# SmartBin.net
KiCad netlist of a schematic drawn in EasyEDA
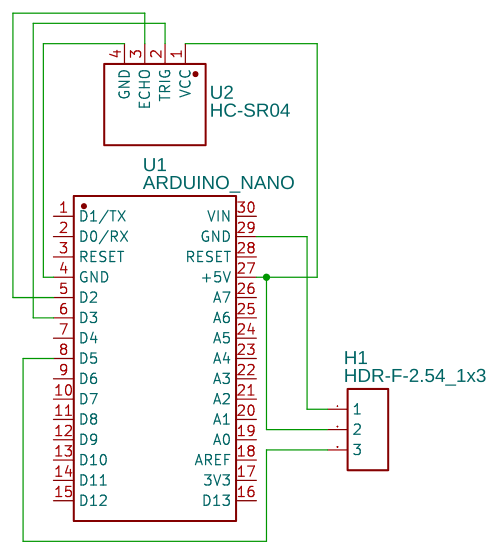
[diagram p0: schematic sheet]

(export (version "E")
  (design (tool "Eeschema 10.0.6"))
  (components
    (comp (ref "H1") (value "HDR-F-2.54_1x3") (libsource (lib "") (part "HDR-F-2.54_1x3")))
    (comp (ref "U1") (value "ARDUINO_NANO") (libsource (lib "") (part "ARDUINO_NANO")))
    (comp (ref "U2")
      (value "HC-SR04")
      (fields (field (name "Manufacturer") "Universal Microelectronics"))
      (libsource (lib "") (part "HC-SR04"))
    )
  )
  (nets
    (net (code "1") (name "Net-(H1-Pad1)") (class "Default")
      (node (ref "H1") (pin "1") (pinfunction "1_1") (pintype "input"))
      (node (ref "U1") (pin "29") (pinfunction "GND_29") (pintype "unspecified"))
    )
    (net (code "2") (name "Net-(U1-+5V)") (class "Default")
      (node (ref "H1") (pin "2") (pinfunction "2_2") (pintype "input"))
      (node (ref "U1") (pin "27") (pinfunction "+5V_27") (pintype "unspecified"))
      (node (ref "U2") (pin "1") (pinfunction "VCC_1") (pintype "unspecified"))
    )
    (net (code "3") (name "Net-(U1-D2)") (class "Default")
      (node (ref "U1") (pin "5") (pinfunction "D2_5") (pintype "unspecified"))
      (node (ref "U2") (pin "3") (pinfunction "ECHO_3") (pintype "unspecified"))
    )
    (net (code "4") (name "Net-(U1-D3)") (class "Default")
      (node (ref "U1") (pin "6") (pinfunction "D3_6") (pintype "unspecified"))
      (node (ref "U2") (pin "2") (pinfunction "TRIG_2") (pintype "unspecified"))
    )
    (net (code "5") (name "Net-(U1-D5)") (class "Default")
      (node (ref "H1") (pin "3") (pinfunction "3_3") (pintype "input"))
      (node (ref "U1") (pin "8") (pinfunction "D5_8") (pintype "unspecified"))
    )
    (net (code "6") (name "Net-(U2-GND)") (class "Default")
      (node (ref "U1") (pin "4") (pinfunction "GND_4") (pintype "unspecified"))
      (node (ref "U2") (pin "4") (pinfunction "GND_4") (pintype "unspecified"))
    )
    (net (code "7") (name "unconnected-(U1-3V3-Pad17)") (class "Default")
      (node (ref "U1") (pin "17") (pinfunction "3V3_17") (pintype "unspecified"))
    )
    (net (code "8") (name "unconnected-(U1-A0-Pad19)") (class "Default")
      (node (ref "U1") (pin "19") (pinfunction "A0_19") (pintype "unspecified"))
    )
    (net (code "9") (name "unconnected-(U1-A1-Pad20)") (class "Default")
      (node (ref "U1") (pin "20") (pinfunction "A1_20") (pintype "unspecified"))
    )
    (net (code "10") (name "unconnected-(U1-A2-Pad21)") (class "Default")
      (node (ref "U1") (pin "21") (pinfunction "A2_21") (pintype "unspecified"))
    )
    (net (code "11") (name "unconnected-(U1-A3-Pad22)") (class "Default")
      (node (ref "U1") (pin "22") (pinfunction "A3_22") (pintype "unspecified"))
    )
    (net (code "12") (name "unconnected-(U1-A4-Pad23)") (class "Default")
      (node (ref "U1") (pin "23") (pinfunction "A4_23") (pintype "unspecified"))
    )
    (net (code "13") (name "unconnected-(U1-A5-Pad24)") (class "Default")
      (node (ref "U1") (pin "24") (pinfunction "A5_24") (pintype "unspecified"))
    )
    (net (code "14") (name "unconnected-(U1-A6-Pad25)") (class "Default")
      (node (ref "U1") (pin "25") (pinfunction "A6_25") (pintype "unspecified"))
    )
    (net (code "15") (name "unconnected-(U1-A7-Pad26)") (class "Default")
      (node (ref "U1") (pin "26") (pinfunction "A7_26") (pintype "unspecified"))
    )
    (net (code "16") (name "unconnected-(U1-AREF-Pad18)") (class "Default")
      (node (ref "U1") (pin "18") (pinfunction "AREF_18") (pintype "unspecified"))
    )
    (net (code "17") (name "unconnected-(U1-D0{slash}RX-Pad2)") (class "Default")
      (node (ref "U1") (pin "2") (pinfunction "D0/RX_2") (pintype "unspecified"))
    )
    (net (code "18") (name "unconnected-(U1-D1{slash}TX-Pad1)") (class "Default")
      (node (ref "U1") (pin "1") (pinfunction "D1/TX_1") (pintype "unspecified"))
    )
    (net (code "19") (name "unconnected-(U1-D4-Pad7)") (class "Default")
      (node (ref "U1") (pin "7") (pinfunction "D4_7") (pintype "unspecified"))
    )
    (net (code "20") (name "unconnected-(U1-D6-Pad9)") (class "Default")
      (node (ref "U1") (pin "9") (pinfunction "D6_9") (pintype "unspecified"))
    )
    (net (code "21") (name "unconnected-(U1-D7-Pad10)") (class "Default")
      (node (ref "U1") (pin "10") (pinfunction "D7_10") (pintype "unspecified"))
    )
    (net (code "22") (name "unconnected-(U1-D8-Pad11)") (class "Default")
      (node (ref "U1") (pin "11") (pinfunction "D8_11") (pintype "unspecified"))
    )
    (net (code "23") (name "unconnected-(U1-D9-Pad12)") (class "Default")
      (node (ref "U1") (pin "12") (pinfunction "D9_12") (pintype "unspecified"))
    )
    (net (code "24") (name "unconnected-(U1-D10-Pad13)") (class "Default")
      (node (ref "U1") (pin "13") (pinfunction "D10_13") (pintype "unspecified"))
    )
    (net (code "25") (name "unconnected-(U1-D11-Pad14)") (class "Default")
      (node (ref "U1") (pin "14") (pinfunction "D11_14") (pintype "unspecified"))
    )
    (net (code "26") (name "unconnected-(U1-D12-Pad15)") (class "Default")
      (node (ref "U1") (pin "15") (pinfunction "D12_15") (pintype "unspecified"))
    )
    (net (code "27") (name "unconnected-(U1-D13-Pad16)") (class "Default")
      (node (ref "U1") (pin "16") (pinfunction "D13_16") (pintype "unspecified"))
    )
    (net (code "28") (name "unconnected-(U1-RESET-Pad3)") (class "Default")
      (node (ref "U1") (pin "3") (pinfunction "RESET_3") (pintype "unspecified"))
    )
    (net (code "29") (name "unconnected-(U1-RESET-Pad28)") (class "Default")
      (node (ref "U1") (pin "28") (pinfunction "RESET_28") (pintype "unspecified"))
    )
    (net (code "30") (name "unconnected-(U1-VIN-Pad30)") (class "Default")
      (node (ref "U1") (pin "30") (pinfunction "VIN_30") (pintype "unspecified"))
    )
  )
)
